# Motor.net
KiCad netlist of a schematic drawn in Altium Designer
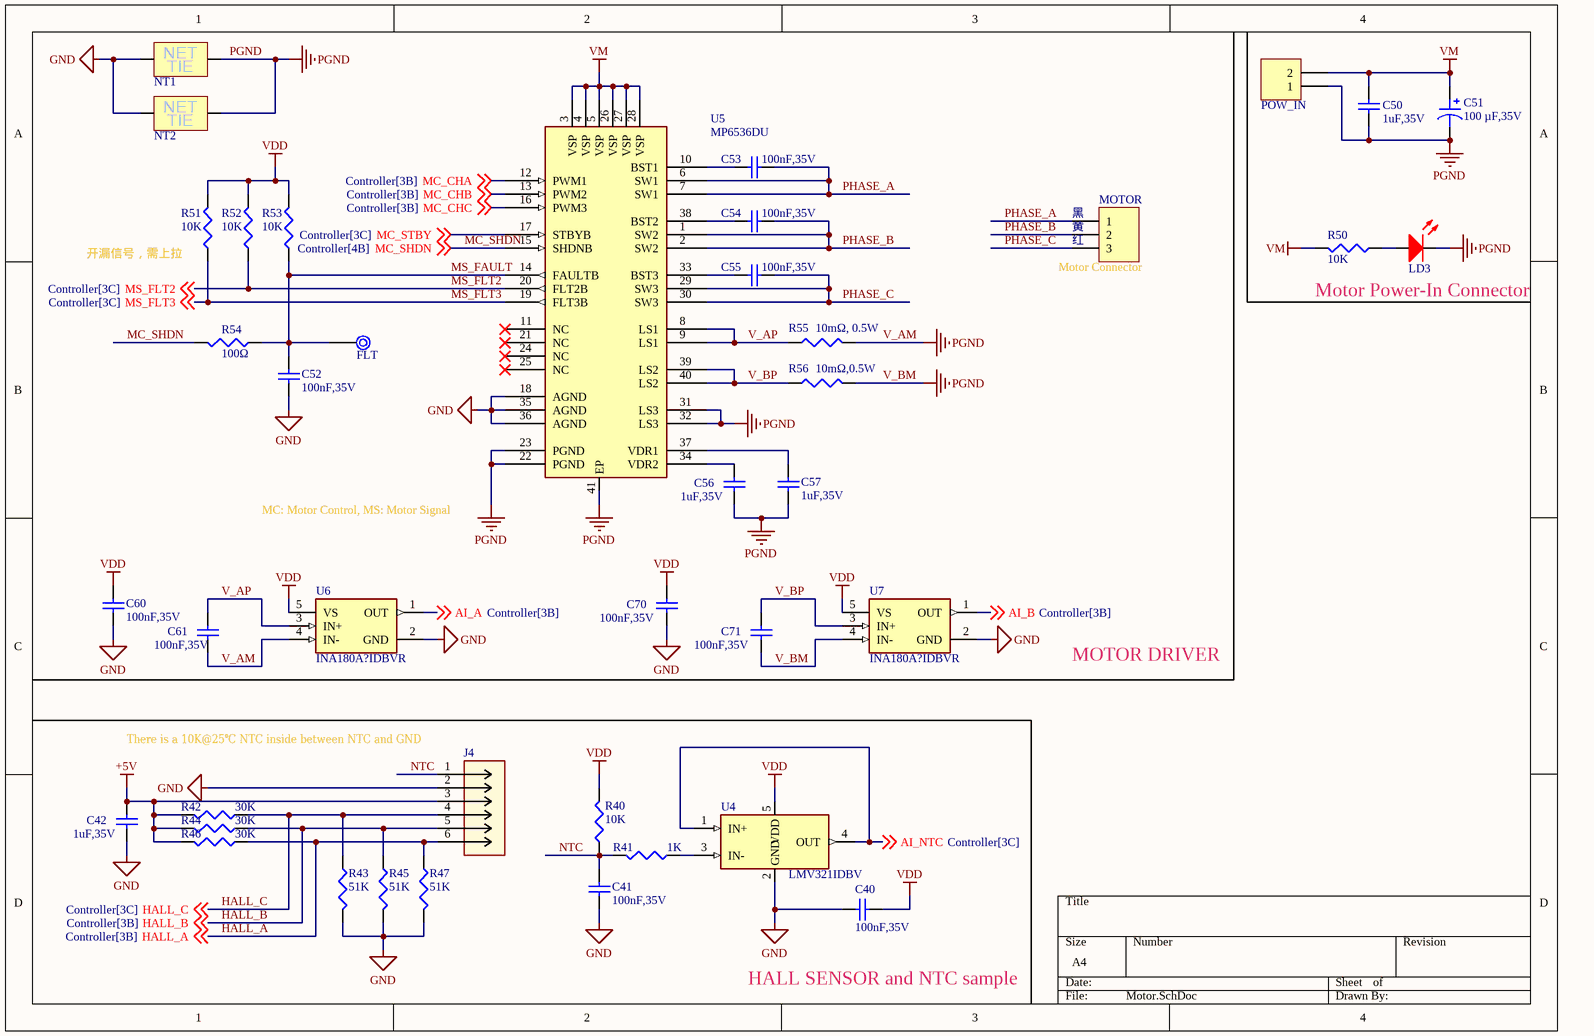
[diagram p0: Motor.SchDoc]

(export (version "E")
  (design (tool "Eeschema 10.0.6"))
  (components
    (comp (ref "C40")
      (value "100nF,35V")
      (footprint "CAPC1005L")
      (description "MLCC, 0402(1005)")
      (fields (field (name "Comment") "MLCC") (field (name "PUBLISHER") "Altium Limited"))
      (libsource (lib "Miscellaneous Devices") (part "Cap"))
    )
    (comp (ref "C41")
      (value "100nF,35V")
      (footprint "CAPC1005L")
      (description "MLCC, 0402(1005)")
      (fields (field (name "Comment") "MLCC") (field (name "PUBLISHER") "Altium Limited"))
      (libsource (lib "Miscellaneous Devices") (part "Cap"))
    )
    (comp (ref "C42")
      (value "1uF,35V")
      (footprint "CAPC1608L")
      (description "MLCC, 0603(1608)")
      (fields (field (name "Comment") "MLCC") (field (name "PUBLISHER") "Altium Limited"))
      (libsource (lib "Miscellaneous Devices") (part "Cap"))
    )
    (comp (ref "C50")
      (value "1uF,35V")
      (footprint "CAPC1608L")
      (description "MLCC, 0603(1608)")
      (fields (field (name "Comment") "MLCC") (field (name "PUBLISHER") "Altium Limited"))
      (libsource (lib "Miscellaneous Devices") (part "Cap"))
    )
    (comp (ref "C51")
      (value "100 µF,35V")
      (footprint "CAP ALSMD 6.6MM H7.7MM")
      (description "CAP ALUM 100UF 20% 35V SMD")
      (fields
        (field (name "PART NUMBER") "EEE-1VA101XAP")
        (field (name "MANUFACTURER") "Panasonic Electronic Components")
      )
      (libsource (lib "Celestial Altium Library - altium_library") (part "Polarised Capacitor"))
    )
    (comp (ref "C52")
      (value "100nF,35V")
      (footprint "CAPC1005L")
      (description "MLCC, 0402(1005)")
      (fields (field (name "Comment") "MLCC") (field (name "PUBLISHER") "Altium Limited"))
      (libsource (lib "Miscellaneous Devices") (part "Cap"))
    )
    (comp (ref "C53")
      (value "100nF,35V")
      (footprint "CAPC1005L")
      (description "MLCC, 0402(1005)")
      (fields (field (name "Comment") "MLCC") (field (name "PUBLISHER") "Altium Limited"))
      (libsource (lib "Miscellaneous Devices") (part "Cap"))
    )
    (comp (ref "C54")
      (value "100nF,35V")
      (footprint "CAPC1005L")
      (description "MLCC, 0402(1005)")
      (fields (field (name "Comment") "MLCC") (field (name "PUBLISHER") "Altium Limited"))
      (libsource (lib "Miscellaneous Devices") (part "Cap"))
    )
    (comp (ref "C55")
      (value "100nF,35V")
      (footprint "CAPC1005L")
      (description "MLCC, 0402(1005)")
      (fields (field (name "Comment") "MLCC") (field (name "PUBLISHER") "Altium Limited"))
      (libsource (lib "Miscellaneous Devices") (part "Cap"))
    )
    (comp (ref "C56")
      (value "1uF,35V")
      (footprint "CAPC1608L")
      (description "MLCC, 0603(1608)")
      (fields (field (name "Comment") "MLCC") (field (name "PUBLISHER") "Altium Limited"))
      (libsource (lib "Miscellaneous Devices") (part "Cap"))
    )
    (comp (ref "C57")
      (value "1uF,35V")
      (footprint "CAPC1608L")
      (description "MLCC, 0603(1608)")
      (fields (field (name "Comment") "MLCC") (field (name "PUBLISHER") "Altium Limited"))
      (libsource (lib "Miscellaneous Devices") (part "Cap"))
    )
    (comp (ref "C60")
      (value "100nF,35V")
      (footprint "CAPC1005L")
      (description "MLCC, 0402(1005)")
      (fields (field (name "Comment") "MLCC") (field (name "PUBLISHER") "Altium Limited"))
      (libsource (lib "Miscellaneous Devices") (part "Cap"))
    )
    (comp (ref "C61")
      (value "100nF,35V")
      (footprint "CAPC1005L")
      (description "MLCC, 0402(1005)")
      (fields (field (name "Comment") "MLCC") (field (name "PUBLISHER") "Altium Limited"))
      (libsource (lib "Miscellaneous Devices") (part "Cap"))
    )
    (comp (ref "C70")
      (value "100nF,35V")
      (footprint "CAPC1005L")
      (description "MLCC, 0402(1005)")
      (fields (field (name "Comment") "MLCC") (field (name "PUBLISHER") "Altium Limited"))
      (libsource (lib "Miscellaneous Devices") (part "Cap"))
    )
    (comp (ref "C71")
      (value "100nF,35V")
      (footprint "CAPC1005L")
      (description "MLCC, 0402(1005)")
      (fields (field (name "Comment") "MLCC") (field (name "PUBLISHER") "Altium Limited"))
      (libsource (lib "Miscellaneous Devices") (part "Cap"))
    )
    (comp (ref "FLT")
      (value "Test Point")
      (footprint "TPSMD-Small")
      (libsource (lib "XSS_IC") (part "TestPoint"))
    )
    (comp (ref "J4")
      (value "530470610")
      (footprint "MOLEX_PicoBlade_53047-0610")
      (libsource (lib "XSS_Connector") (part "MOLEX_PicoBlade_53047-0610"))
    )
    (comp (ref "LD3")
      (value "LED")
      (footprint "LED_0603_AK_Red")
      (description "RED LED, 0603")
      (libsource (lib "XSS_IC") (part "LED_0603_RED"))
    )
    (comp (ref "MOTOR")
      (value "B3B-XH-A")
      (footprint "B3B-XH-A")
      (description "JST XH Series, Pitch 2.5mm, Top Entry, 3Pins")
      (libsource (lib "XSS_Connector") (part "B3B-XH-A"))
    )
    (comp (ref "NT1")
      (value "Net Tie")
      (footprint "NET-TIE-50MIL-Block")
      (libsource (lib "XSS_IC") (part "NET-TIE-GROUND"))
    )
    (comp (ref "NT2")
      (value "Net Tie")
      (footprint "NET-TIE-50MIL-Block")
      (libsource (lib "XSS_IC") (part "NET-TIE-GROUND"))
    )
    (comp (ref "POW_IN")
      (value "5267-02A")
      (footprint "Molex-5267-02a")
      (libsource (lib "XSS_Connector") (part "Molex-5267-02A"))
    )
    (comp (ref "R40")
      (value "10K")
      (footprint "RESC1005L")
      (description "Resistor, 0402(1005)")
      (fields (field (name "Comment") "RES, SMT") (field (name "PUBLISHER") "Altium Limited"))
      (libsource (lib "Miscellaneous Devices") (part "Res3"))
    )
    (comp (ref "R41")
      (value "1K")
      (footprint "RESC1005L")
      (description "Resistor, 0402(1005)")
      (fields (field (name "Comment") "RES, SMT") (field (name "PUBLISHER") "Altium Limited"))
      (libsource (lib "Miscellaneous Devices") (part "Res3"))
    )
    (comp (ref "R42")
      (value "30K")
      (footprint "RESC1005L")
      (description "Resistor, 0402(1005)")
      (fields (field (name "Comment") "RES, SMT") (field (name "PUBLISHER") "Altium Limited"))
      (libsource (lib "Miscellaneous Devices") (part "Res3"))
    )
    (comp (ref "R43")
      (value "51K")
      (footprint "RESC1005L")
      (description "Resistor, 0402(1005)")
      (fields (field (name "Comment") "RES, SMT") (field (name "PUBLISHER") "Altium Limited"))
      (libsource (lib "Miscellaneous Devices") (part "Res3"))
    )
    (comp (ref "R44")
      (value "30K")
      (footprint "RESC1005L")
      (description "Resistor, 0402(1005)")
      (fields (field (name "Comment") "RES, SMT") (field (name "PUBLISHER") "Altium Limited"))
      (libsource (lib "Miscellaneous Devices") (part "Res3"))
    )
    (comp (ref "R45")
      (value "51K")
      (footprint "RESC1005L")
      (description "Resistor, 0402(1005)")
      (fields (field (name "Comment") "RES, SMT") (field (name "PUBLISHER") "Altium Limited"))
      (libsource (lib "Miscellaneous Devices") (part "Res3"))
    )
    (comp (ref "R46")
      (value "30K")
      (footprint "RESC1005L")
      (description "Resistor, 0402(1005)")
      (fields (field (name "Comment") "RES, SMT") (field (name "PUBLISHER") "Altium Limited"))
      (libsource (lib "Miscellaneous Devices") (part "Res3"))
    )
    (comp (ref "R47")
      (value "51K")
      (footprint "RESC1005L")
      (description "Resistor, 0402(1005)")
      (fields (field (name "Comment") "RES, SMT") (field (name "PUBLISHER") "Altium Limited"))
      (libsource (lib "Miscellaneous Devices") (part "Res3"))
    )
    (comp (ref "R50")
      (value "10K")
      (footprint "RESC1005L")
      (description "Resistor, 0402(1005)")
      (fields (field (name "Comment") "RES, SMT") (field (name "PUBLISHER") "Altium Limited"))
      (libsource (lib "Miscellaneous Devices") (part "Res3"))
    )
    (comp (ref "R51")
      (value "10K")
      (footprint "RESC1005L")
      (description "Resistor, 0402(1005)")
      (fields (field (name "Comment") "RES, SMT") (field (name "PUBLISHER") "Altium Limited"))
      (libsource (lib "Miscellaneous Devices") (part "Res3"))
    )
    (comp (ref "R52")
      (value "10K")
      (footprint "RESC1005L")
      (description "Resistor, 0402(1005)")
      (fields (field (name "Comment") "RES, SMT") (field (name "PUBLISHER") "Altium Limited"))
      (libsource (lib "Miscellaneous Devices") (part "Res3"))
    )
    (comp (ref "R53")
      (value "10K")
      (footprint "RESC1005L")
      (description "Resistor, 0402(1005)")
      (fields (field (name "Comment") "RES, SMT") (field (name "PUBLISHER") "Altium Limited"))
      (libsource (lib "Miscellaneous Devices") (part "Res3"))
    )
    (comp (ref "R54")
      (value "100Ω")
      (footprint "RESC1005L")
      (description "Resistor, 0402(1005)")
      (fields (field (name "Comment") "RES, SMT") (field (name "PUBLISHER") "Altium Limited"))
      (libsource (lib "Miscellaneous Devices") (part "Res3"))
    )
    (comp (ref "R55")
      (value "10mΩ, 0.5W")
      (footprint "RESC2012L")
      (description "Resistor, 0805(2012)")
      (fields (field (name "Comment") "RES, SMT") (field (name "PUBLISHER") "Altium Limited"))
      (libsource (lib "Miscellaneous Devices") (part "Res3"))
    )
    (comp (ref "R56")
      (value "10mΩ,0.5W")
      (footprint "RESC2012L")
      (description "Resistor, 0805(2012)")
      (fields (field (name "Comment") "RES, SMT") (field (name "PUBLISHER") "Altium Limited"))
      (libsource (lib "Miscellaneous Devices") (part "Res3"))
    )
    (comp (ref "U4")
      (value "LMV321IDBV")
      (footprint "TI_DBV0005A")
      (description "LMV321, Single, 5.5-V, 1-MHz, RRO operational amplifier, SOT-23-5(DBV) package")
      (libsource (lib "XSS_IC") (part "LMV321IDBV"))
    )
    (comp (ref "U5")
      (value "MP6536DU")
      (footprint "QFN40-5x5_MP6536")
      (description "MPS, MP6536DU-LF-P/Z, 26V, 5.5A, 3-Channel Half-Bridge Driver, QFN40 5mmx5mm package")
      (libsource (lib "XSS_IC") (part "MP6536DU"))
    )
    (comp (ref "U6")
      (value "INA180A?IDBVR")
      (footprint "TI_DBV0005A")
      (description "TI, 26V, 350kHz current sense amplifier, 1 Channel, DBV Package")
      (libsource (lib "XSS_IC") (part "INA180A?IDBVR"))
    )
    (comp (ref "U7")
      (value "INA180A?IDBVR")
      (footprint "TI_DBV0005A")
      (description "TI, 26V, 350kHz current sense amplifier, 1 Channel, DBV Package")
      (libsource (lib "XSS_IC") (part "INA180A?IDBVR"))
    )
  )
  (nets
    (net (code "1") (name "+5V") (class "Default")
      (node (ref "C42") (pin "1") (pinfunction "1_1") (pintype "passive"))
      (node (ref "J4") (pin "3") (pinfunction "3_3") (pintype "passive"))
      (node (ref "R42") (pin "2") (pinfunction "2_2") (pintype "passive"))
      (node (ref "R44") (pin "2") (pinfunction "2_2") (pintype "passive"))
      (node (ref "R46") (pin "2") (pinfunction "2_2") (pintype "passive"))
    )
    (net (code "2") (name "/MS_FAULT") (class "Default")
      (node (ref "C52") (pin "1") (pinfunction "1_1") (pintype "passive"))
      (node (ref "FLT") (pin "1") (pinfunction "1_1") (pintype "passive"))
      (node (ref "R53") (pin "1") (pinfunction "1_1") (pintype "passive"))
      (node (ref "R54") (pin "1") (pinfunction "1_1") (pintype "passive"))
      (node (ref "U5") (pin "14") (pinfunction "FAULTB_14") (pintype "output"))
    )
    (net (code "3") (name "/NTC") (class "Default")
      (node (ref "C41") (pin "1") (pinfunction "1_1") (pintype "passive"))
      (node (ref "J4") (pin "1") (pinfunction "1_1") (pintype "passive"))
      (node (ref "R40") (pin "1") (pinfunction "1_1") (pintype "passive"))
      (node (ref "R41") (pin "2") (pinfunction "2_2") (pintype "passive"))
    )
    (net (code "4") (name "/PHASE_A") (class "Default")
      (node (ref "C53") (pin "1") (pinfunction "1_1") (pintype "passive"))
      (node (ref "MOTOR") (pin "1") (pinfunction "1_1") (pintype "passive"))
      (node (ref "U5") (pin "6") (pinfunction "SW1_6") (pintype "passive"))
      (node (ref "U5") (pin "7") (pinfunction "SW1_7") (pintype "passive"))
    )
    (net (code "5") (name "/PHASE_B") (class "Default")
      (node (ref "C54") (pin "1") (pinfunction "1_1") (pintype "passive"))
      (node (ref "MOTOR") (pin "2") (pinfunction "2_2") (pintype "passive"))
      (node (ref "U5") (pin "1") (pinfunction "SW2_1") (pintype "passive"))
      (node (ref "U5") (pin "2") (pinfunction "SW2_2") (pintype "passive"))
    )
    (net (code "6") (name "/PHASE_C") (class "Default")
      (node (ref "C55") (pin "1") (pinfunction "1_1") (pintype "passive"))
      (node (ref "MOTOR") (pin "3") (pinfunction "3_3") (pintype "passive"))
      (node (ref "U5") (pin "29") (pinfunction "SW3_29") (pintype "passive"))
      (node (ref "U5") (pin "30") (pinfunction "SW3_30") (pintype "passive"))
    )
    (net (code "7") (name "/V_AP") (class "Default")
      (node (ref "C61") (pin "1") (pinfunction "1_1") (pintype "passive"))
      (node (ref "R55") (pin "1") (pinfunction "1_1") (pintype "passive"))
      (node (ref "U5") (pin "8") (pinfunction "LS1_8") (pintype "passive"))
      (node (ref "U5") (pin "9") (pinfunction "LS1_9") (pintype "passive"))
      (node (ref "U6") (pin "3") (pinfunction "IN+_3") (pintype "input"))
    )
    (net (code "8") (name "/V_BP") (class "Default")
      (node (ref "C71") (pin "1") (pinfunction "1_1") (pintype "passive"))
      (node (ref "R56") (pin "1") (pinfunction "1_1") (pintype "passive"))
      (node (ref "U5") (pin "39") (pinfunction "LS2_39") (pintype "passive"))
      (node (ref "U5") (pin "40") (pinfunction "LS2_40") (pintype "passive"))
      (node (ref "U7") (pin "3") (pinfunction "IN+_3") (pintype "input"))
    )
    (net (code "9") (name "AI_A") (class "Default")
      (node (ref "U6") (pin "1") (pinfunction "OUT_1") (pintype "output"))
    )
    (net (code "10") (name "AI_B") (class "Default")
      (node (ref "U7") (pin "1") (pinfunction "OUT_1") (pintype "output"))
    )
    (net (code "11") (name "AI_NTC") (class "Default")
      (node (ref "U4") (pin "1") (pinfunction "IN+_1") (pintype "input"))
      (node (ref "U4") (pin "4") (pinfunction "OUT_4") (pintype "output"))
    )
    (net (code "12") (name "GND") (class "Default")
      (node (ref "C40") (pin "1") (pinfunction "1_1") (pintype "passive"))
      (node (ref "C41") (pin "2") (pinfunction "2_2") (pintype "passive"))
      (node (ref "C42") (pin "2") (pinfunction "2_2") (pintype "passive"))
      (node (ref "C52") (pin "2") (pinfunction "2_2") (pintype "passive"))
      (node (ref "C60") (pin "2") (pinfunction "2_2") (pintype "passive"))
      (node (ref "C70") (pin "2") (pinfunction "2_2") (pintype "passive"))
      (node (ref "J4") (pin "2") (pinfunction "2_2") (pintype "passive"))
      (node (ref "NT1") (pin "1") (pinfunction "AG_1") (pintype "passive"))
      (node (ref "NT2") (pin "1") (pinfunction "AG_1") (pintype "passive"))
      (node (ref "R43") (pin "2") (pinfunction "2_2") (pintype "passive"))
      (node (ref "R45") (pin "2") (pinfunction "2_2") (pintype "passive"))
      (node (ref "R47") (pin "2") (pinfunction "2_2") (pintype "passive"))
      (node (ref "U4") (pin "2") (pinfunction "GND_2") (pintype "power_in"))
      (node (ref "U5") (pin "18") (pinfunction "AGND_18") (pintype "power_in"))
      (node (ref "U5") (pin "35") (pinfunction "AGND_35") (pintype "power_in"))
      (node (ref "U5") (pin "36") (pinfunction "AGND_36") (pintype "power_in"))
      (node (ref "U6") (pin "2") (pinfunction "GND_2") (pintype "power_in"))
      (node (ref "U7") (pin "2") (pinfunction "GND_2") (pintype "power_in"))
    )
    (net (code "13") (name "HALL_A") (class "Default")
      (node (ref "J4") (pin "6") (pinfunction "6_6") (pintype "passive"))
      (node (ref "R46") (pin "1") (pinfunction "1_1") (pintype "passive"))
      (node (ref "R47") (pin "1") (pinfunction "1_1") (pintype "passive"))
    )
    (net (code "14") (name "HALL_B") (class "Default")
      (node (ref "J4") (pin "5") (pinfunction "5_5") (pintype "passive"))
      (node (ref "R44") (pin "1") (pinfunction "1_1") (pintype "passive"))
      (node (ref "R45") (pin "1") (pinfunction "1_1") (pintype "passive"))
    )
    (net (code "15") (name "HALL_C") (class "Default")
      (node (ref "J4") (pin "4") (pinfunction "4_4") (pintype "passive"))
      (node (ref "R42") (pin "1") (pinfunction "1_1") (pintype "passive"))
      (node (ref "R43") (pin "1") (pinfunction "1_1") (pintype "passive"))
    )
    (net (code "16") (name "MC_CHA") (class "Default")
      (node (ref "U5") (pin "12") (pinfunction "PWM1_12") (pintype "input"))
    )
    (net (code "17") (name "MC_CHB") (class "Default")
      (node (ref "U5") (pin "13") (pinfunction "PWM2_13") (pintype "input"))
    )
    (net (code "18") (name "MC_CHC") (class "Default")
      (node (ref "U5") (pin "16") (pinfunction "PWM3_16") (pintype "input"))
    )
    (net (code "19") (name "MC_SHDN") (class "Default")
      (node (ref "R54") (pin "2") (pinfunction "2_2") (pintype "passive"))
      (node (ref "U5") (pin "15") (pinfunction "SHDNB_15") (pintype "input"))
    )
    (net (code "20") (name "MC_STBY") (class "Default")
      (node (ref "U5") (pin "17") (pinfunction "STBYB_17") (pintype "input"))
    )
    (net (code "21") (name "MS_FLT2") (class "Default")
      (node (ref "R52") (pin "1") (pinfunction "1_1") (pintype "passive"))
      (node (ref "U5") (pin "20") (pinfunction "FLT2B_20") (pintype "output"))
    )
    (net (code "22") (name "MS_FLT3") (class "Default")
      (node (ref "R51") (pin "1") (pinfunction "1_1") (pintype "passive"))
      (node (ref "U5") (pin "19") (pinfunction "FLT3B_19") (pintype "output"))
    )
    (net (code "23") (name "Net-(LD3-PadA)") (class "Default")
      (node (ref "LD3") (pin "A") (pinfunction "A_A") (pintype "passive"))
      (node (ref "R50") (pin "1") (pinfunction "1_1") (pintype "passive"))
    )
    (net (code "24") (name "Net-(U4-IN-)") (class "Default")
      (node (ref "R41") (pin "1") (pinfunction "1_1") (pintype "passive"))
      (node (ref "U4") (pin "3") (pinfunction "IN-_3") (pintype "input"))
    )
    (net (code "25") (name "Net-(U5-BST1)") (class "Default")
      (node (ref "C53") (pin "2") (pinfunction "2_2") (pintype "passive"))
      (node (ref "U5") (pin "10") (pinfunction "BST1_10") (pintype "passive"))
    )
    (net (code "26") (name "Net-(U5-BST2)") (class "Default")
      (node (ref "C54") (pin "2") (pinfunction "2_2") (pintype "passive"))
      (node (ref "U5") (pin "38") (pinfunction "BST2_38") (pintype "passive"))
    )
    (net (code "27") (name "Net-(U5-BST3)") (class "Default")
      (node (ref "C55") (pin "2") (pinfunction "2_2") (pintype "passive"))
      (node (ref "U5") (pin "33") (pinfunction "BST3_33") (pintype "passive"))
    )
    (net (code "28") (name "Net-(U5-VDR1)") (class "Default")
      (node (ref "C57") (pin "1") (pinfunction "1_1") (pintype "passive"))
      (node (ref "U5") (pin "37") (pinfunction "VDR1_37") (pintype "passive"))
    )
    (net (code "29") (name "Net-(U5-VDR2)") (class "Default")
      (node (ref "C56") (pin "1") (pinfunction "1_1") (pintype "passive"))
      (node (ref "U5") (pin "34") (pinfunction "VDR2_34") (pintype "passive"))
    )
    (net (code "30") (name "PGND") (class "Default")
      (node (ref "C50") (pin "1") (pinfunction "1_1") (pintype "passive"))
      (node (ref "C51") (pin "2") (pinfunction "2_2") (pintype "passive"))
      (node (ref "C56") (pin "2") (pinfunction "2_2") (pintype "passive"))
      (node (ref "C57") (pin "2") (pinfunction "2_2") (pintype "passive"))
      (node (ref "C61") (pin "2") (pinfunction "2_2") (pintype "passive"))
      (node (ref "C71") (pin "2") (pinfunction "2_2") (pintype "passive"))
      (node (ref "LD3") (pin "K") (pinfunction "K_K") (pintype "passive"))
      (node (ref "NT1") (pin "2") (pinfunction "G_2") (pintype "passive"))
      (node (ref "NT2") (pin "2") (pinfunction "G_2") (pintype "passive"))
      (node (ref "POW_IN") (pin "1") (pinfunction "1_1") (pintype "passive"))
      (node (ref "R55") (pin "2") (pinfunction "2_2") (pintype "passive"))
      (node (ref "R56") (pin "2") (pinfunction "2_2") (pintype "passive"))
      (node (ref "U5") (pin "22") (pinfunction "PGND_22") (pintype "power_in"))
      (node (ref "U5") (pin "23") (pinfunction "PGND_23") (pintype "power_in"))
      (node (ref "U5") (pin "31") (pinfunction "LS3_31") (pintype "passive"))
      (node (ref "U5") (pin "32") (pinfunction "LS3_32") (pintype "passive"))
      (node (ref "U5") (pin "41") (pinfunction "EP_41") (pintype "passive"))
      (node (ref "U6") (pin "4") (pinfunction "IN-_4") (pintype "input"))
      (node (ref "U7") (pin "4") (pinfunction "IN-_4") (pintype "input"))
    )
    (net (code "31") (name "VDD") (class "Default")
      (node (ref "C40") (pin "2") (pinfunction "2_2") (pintype "passive"))
      (node (ref "C60") (pin "1") (pinfunction "1_1") (pintype "passive"))
      (node (ref "C70") (pin "1") (pinfunction "1_1") (pintype "passive"))
      (node (ref "R40") (pin "2") (pinfunction "2_2") (pintype "passive"))
      (node (ref "R51") (pin "2") (pinfunction "2_2") (pintype "passive"))
      (node (ref "R52") (pin "2") (pinfunction "2_2") (pintype "passive"))
      (node (ref "R53") (pin "2") (pinfunction "2_2") (pintype "passive"))
      (node (ref "U4") (pin "5") (pinfunction "VDD_5") (pintype "power_in"))
      (node (ref "U6") (pin "5") (pinfunction "VS_5") (pintype "power_in"))
      (node (ref "U7") (pin "5") (pinfunction "VS_5") (pintype "power_in"))
    )
    (net (code "32") (name "VM") (class "Default")
      (node (ref "C50") (pin "2") (pinfunction "2_2") (pintype "passive"))
      (node (ref "C51") (pin "1") (pinfunction "1_1") (pintype "passive"))
      (node (ref "POW_IN") (pin "2") (pinfunction "2_2") (pintype "passive"))
      (node (ref "R50") (pin "2") (pinfunction "2_2") (pintype "passive"))
      (node (ref "U5") (pin "26") (pinfunction "VSP_26") (pintype "power_in"))
      (node (ref "U5") (pin "27") (pinfunction "VSP_27") (pintype "power_in"))
      (node (ref "U5") (pin "28") (pinfunction "VSP_28") (pintype "power_in"))
      (node (ref "U5") (pin "3") (pinfunction "VSP_3") (pintype "power_in"))
      (node (ref "U5") (pin "4") (pinfunction "VSP_4") (pintype "power_in"))
      (node (ref "U5") (pin "5") (pinfunction "VSP_5") (pintype "power_in"))
    )
    (net (code "33") (name "unconnected-(U5-NC-Pad11)") (class "Default")
      (node (ref "U5") (pin "11") (pinfunction "NC_11") (pintype "passive+no_connect"))
    )
    (net (code "34") (name "unconnected-(U5-NC-Pad21)") (class "Default")
      (node (ref "U5") (pin "21") (pinfunction "NC_21") (pintype "passive+no_connect"))
    )
    (net (code "35") (name "unconnected-(U5-NC-Pad24)") (class "Default")
      (node (ref "U5") (pin "24") (pinfunction "NC_24") (pintype "passive+no_connect"))
    )
    (net (code "36") (name "unconnected-(U5-NC-Pad25)") (class "Default")
      (node (ref "U5") (pin "25") (pinfunction "NC_25") (pintype "passive+no_connect"))
    )
  )
)
